# USB_Hub.net
KiCad netlist of a schematic drawn in Altium Designer
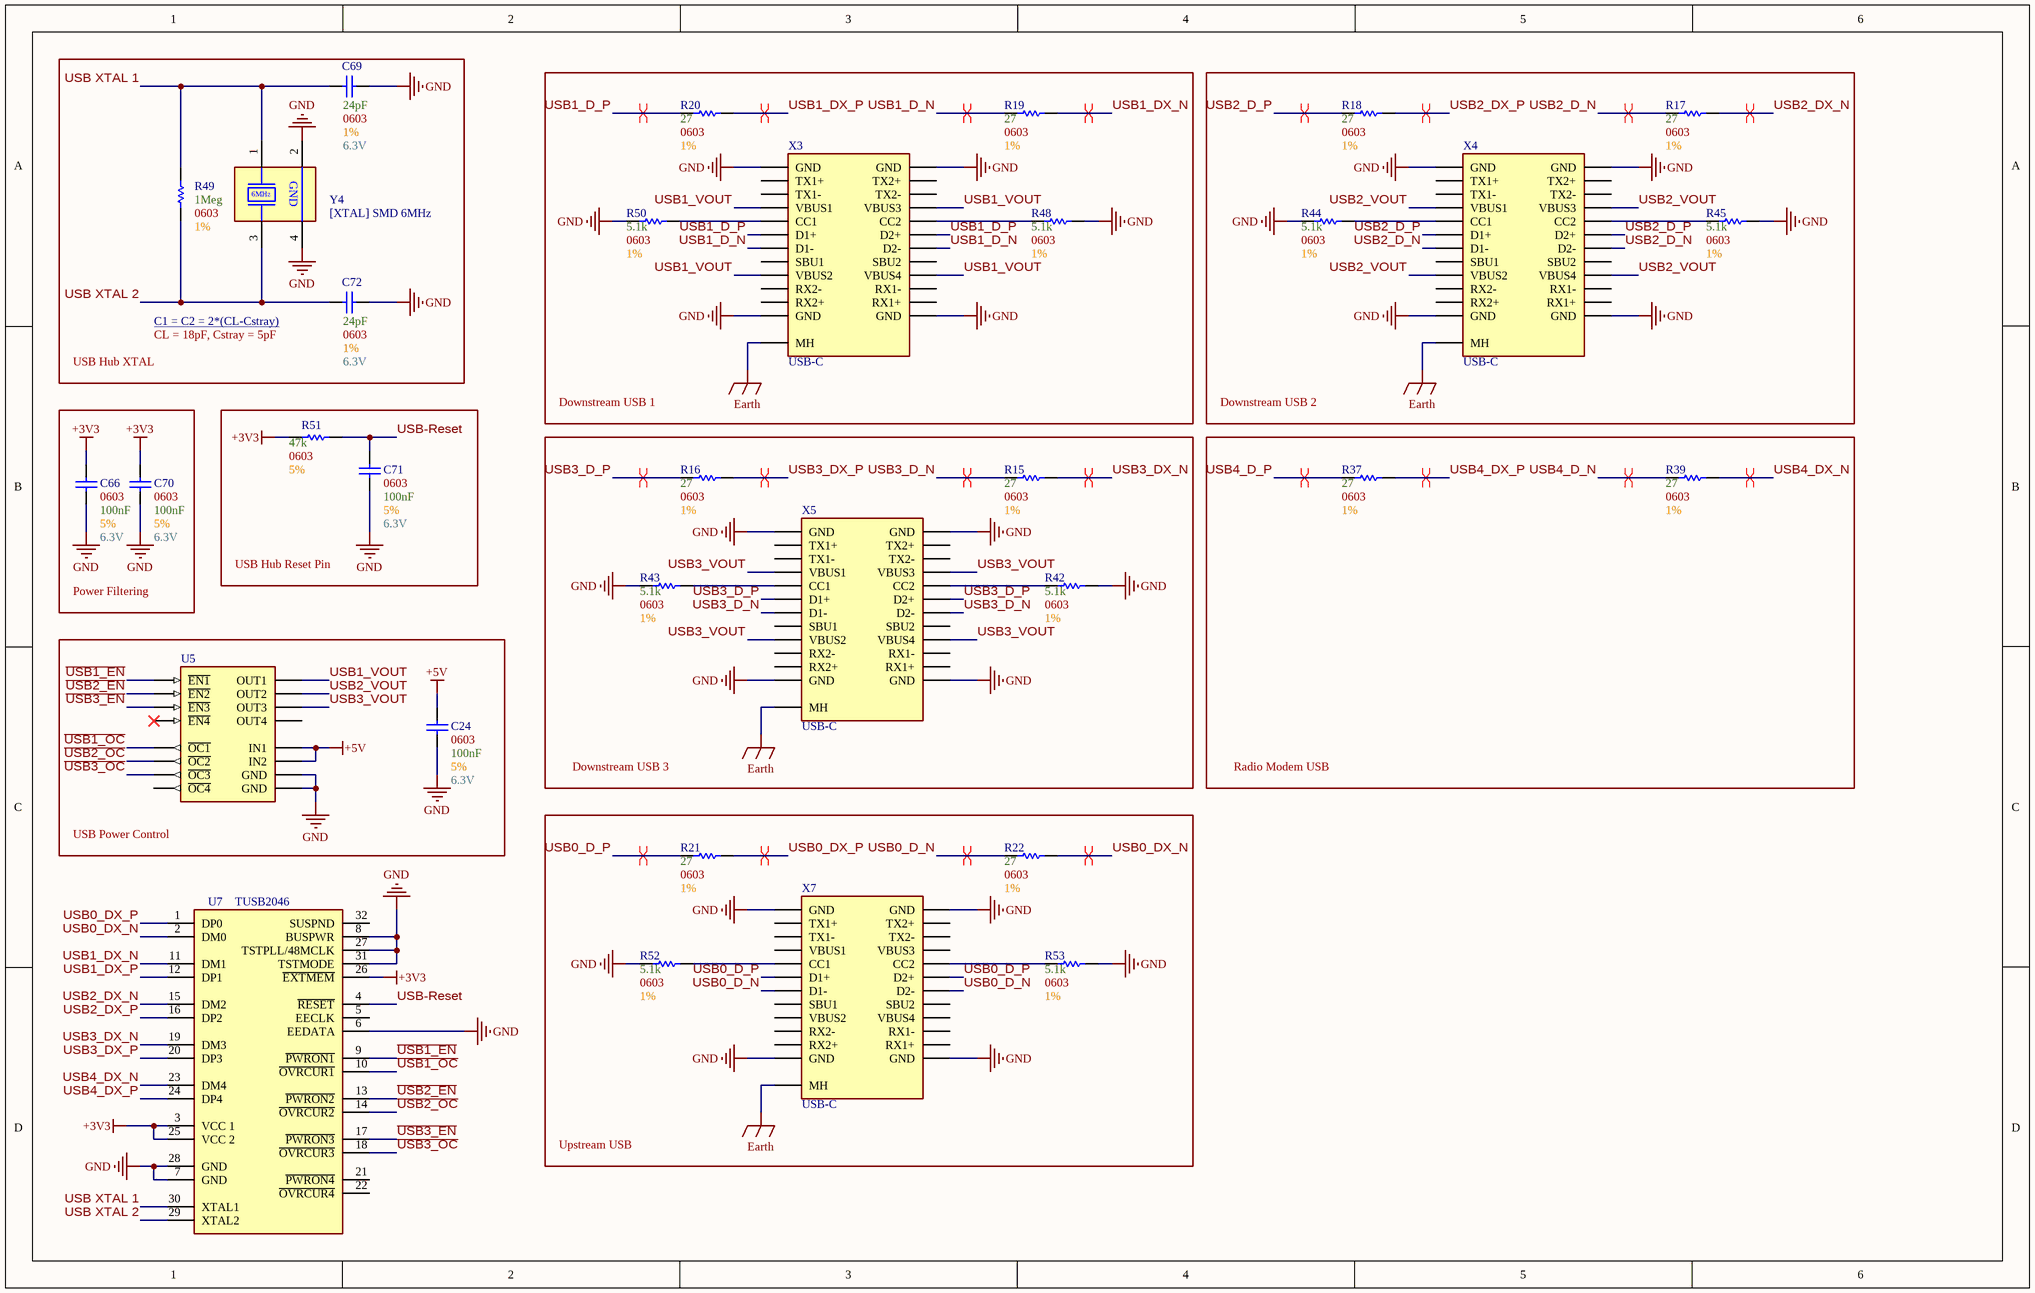
[diagram p0: USB Hub.SchDoc]

(export (version "E")
  (design (tool "Eeschema 10.0.6"))
  (components
    (comp (ref "C24")
      (value "[Cap] SMD Nonpolarized")
      (footprint "[Cap] SMD 0603")
      (fields
        (field (name "SIZE PACKAGE") "0603")
        (field (name "CAPACITANCE") "100nF")
        (field (name "VOLTAGE") "6.3V")
        (field (name "TOLERANCE") "5%")
      )
      (libsource (lib "RADM Components") (part "[Cap] SMD Nonpolarized"))
    )
    (comp (ref "C66")
      (value "[Cap] SMD Nonpolarized")
      (footprint "[Cap] SMD 0603")
      (fields
        (field (name "SIZE PACKAGE") "0603")
        (field (name "CAPACITANCE") "100nF")
        (field (name "VOLTAGE") "6.3V")
        (field (name "TOLERANCE") "5%")
      )
      (libsource (lib "RADM Components") (part "[Cap] SMD Nonpolarized"))
    )
    (comp (ref "C69")
      (value "SMD Nonpolarized")
      (footprint "[Cap] SMD 0603")
      (fields
        (field (name "TOLERANCE") "1%")
        (field (name "SIZE PACKAGE") "0603")
        (field (name "CAPACITANCE") "24pF")
        (field (name "VOLTAGE") "6.3V")
      )
      (libsource (lib "RADM Components") (part "[Cap] SMD Nonpolarized"))
    )
    (comp (ref "C70")
      (value "[Cap] SMD Nonpolarized")
      (footprint "[Cap] SMD 0603")
      (fields
        (field (name "SIZE PACKAGE") "0603")
        (field (name "CAPACITANCE") "100nF")
        (field (name "VOLTAGE") "6.3V")
        (field (name "TOLERANCE") "5%")
      )
      (libsource (lib "RADM Components") (part "[Cap] SMD Nonpolarized"))
    )
    (comp (ref "C71")
      (value "[Cap] SMD Nonpolarized")
      (footprint "[Cap] SMD 0603")
      (fields
        (field (name "SIZE PACKAGE") "0603")
        (field (name "CAPACITANCE") "100nF")
        (field (name "VOLTAGE") "6.3V")
        (field (name "TOLERANCE") "5%")
      )
      (libsource (lib "RADM Components") (part "[Cap] SMD Nonpolarized"))
    )
    (comp (ref "C72")
      (value "SMD Nonpolarized")
      (footprint "[Cap] SMD 0603")
      (fields
        (field (name "TOLERANCE") "1%")
        (field (name "SIZE PACKAGE") "0603")
        (field (name "CAPACITANCE") "24pF")
        (field (name "VOLTAGE") "6.3V")
      )
      (libsource (lib "RADM Components") (part "[Cap] SMD Nonpolarized"))
    )
    (comp (ref "R15")
      (value "[Res] SMD Resistor")
      (footprint "[Res] SMD 0603")
      (description "Generic")
      (fields
        (field (name "TOLERANCE") "1%")
        (field (name "RESISTANCE") "27")
        (field (name "SIZE PACKAGE") "0603")
      )
      (libsource (lib "RADM Components") (part "[Res] SMD Resistor"))
    )
    (comp (ref "R16")
      (value "[Res] SMD Resistor")
      (footprint "[Res] SMD 0603")
      (description "Generic")
      (fields
        (field (name "TOLERANCE") "1%")
        (field (name "RESISTANCE") "27")
        (field (name "SIZE PACKAGE") "0603")
      )
      (libsource (lib "RADM Components") (part "[Res] SMD Resistor"))
    )
    (comp (ref "R17")
      (value "[Res] SMD Resistor")
      (footprint "[Res] SMD 0603")
      (description "Generic")
      (fields
        (field (name "TOLERANCE") "1%")
        (field (name "RESISTANCE") "27")
        (field (name "SIZE PACKAGE") "0603")
      )
      (libsource (lib "RADM Components") (part "[Res] SMD Resistor"))
    )
    (comp (ref "R18")
      (value "[Res] SMD Resistor")
      (footprint "[Res] SMD 0603")
      (description "Generic")
      (fields
        (field (name "TOLERANCE") "1%")
        (field (name "RESISTANCE") "27")
        (field (name "SIZE PACKAGE") "0603")
      )
      (libsource (lib "RADM Components") (part "[Res] SMD Resistor"))
    )
    (comp (ref "R19")
      (value "[Res] SMD Resistor")
      (footprint "[Res] SMD 0603")
      (description "Generic")
      (fields
        (field (name "TOLERANCE") "1%")
        (field (name "RESISTANCE") "27")
        (field (name "SIZE PACKAGE") "0603")
      )
      (libsource (lib "RADM Components") (part "[Res] SMD Resistor"))
    )
    (comp (ref "R20")
      (value "[Res] SMD Resistor")
      (footprint "[Res] SMD 0603")
      (description "Generic")
      (fields
        (field (name "TOLERANCE") "1%")
        (field (name "RESISTANCE") "27")
        (field (name "SIZE PACKAGE") "0603")
      )
      (libsource (lib "RADM Components") (part "[Res] SMD Resistor"))
    )
    (comp (ref "R21")
      (value "[Res] SMD Resistor")
      (footprint "[Res] SMD 0603")
      (description "Generic")
      (fields
        (field (name "TOLERANCE") "1%")
        (field (name "RESISTANCE") "27")
        (field (name "SIZE PACKAGE") "0603")
      )
      (libsource (lib "RADM Components") (part "[Res] SMD Resistor"))
    )
    (comp (ref "R22")
      (value "[Res] SMD Resistor")
      (footprint "[Res] SMD 0603")
      (description "Generic")
      (fields
        (field (name "TOLERANCE") "1%")
        (field (name "RESISTANCE") "27")
        (field (name "SIZE PACKAGE") "0603")
      )
      (libsource (lib "RADM Components") (part "[Res] SMD Resistor"))
    )
    (comp (ref "R37")
      (value "[Res] SMD Resistor")
      (footprint "[Res] SMD 0603")
      (description "Generic")
      (fields
        (field (name "TOLERANCE") "1%")
        (field (name "RESISTANCE") "27")
        (field (name "SIZE PACKAGE") "0603")
      )
      (libsource (lib "RADM Components") (part "[Res] SMD Resistor"))
    )
    (comp (ref "R39")
      (value "[Res] SMD Resistor")
      (footprint "[Res] SMD 0603")
      (description "Generic")
      (fields
        (field (name "TOLERANCE") "1%")
        (field (name "RESISTANCE") "27")
        (field (name "SIZE PACKAGE") "0603")
      )
      (libsource (lib "RADM Components") (part "[Res] SMD Resistor"))
    )
    (comp (ref "R42")
      (value "[Res] SMD Resistor")
      (footprint "[Res] SMD 0603")
      (description "Generic")
      (fields
        (field (name "TOLERANCE") "1%")
        (field (name "RESISTANCE") "5.1k")
        (field (name "SIZE PACKAGE") "0603")
      )
      (libsource (lib "RADM Components") (part "[Res] SMD Resistor"))
    )
    (comp (ref "R43")
      (value "[Res] SMD Resistor")
      (footprint "[Res] SMD 0603")
      (description "Generic")
      (fields
        (field (name "TOLERANCE") "1%")
        (field (name "RESISTANCE") "5.1k")
        (field (name "SIZE PACKAGE") "0603")
      )
      (libsource (lib "RADM Components") (part "[Res] SMD Resistor"))
    )
    (comp (ref "R44")
      (value "[Res] SMD Resistor")
      (footprint "[Res] SMD 0603")
      (description "Generic")
      (fields
        (field (name "TOLERANCE") "1%")
        (field (name "RESISTANCE") "5.1k")
        (field (name "SIZE PACKAGE") "0603")
      )
      (libsource (lib "RADM Components") (part "[Res] SMD Resistor"))
    )
    (comp (ref "R45")
      (value "[Res] SMD Resistor")
      (footprint "[Res] SMD 0603")
      (description "Generic")
      (fields
        (field (name "TOLERANCE") "1%")
        (field (name "RESISTANCE") "5.1k")
        (field (name "SIZE PACKAGE") "0603")
      )
      (libsource (lib "RADM Components") (part "[Res] SMD Resistor"))
    )
    (comp (ref "R48")
      (value "[Res] SMD Resistor")
      (footprint "[Res] SMD 0603")
      (description "Generic")
      (fields
        (field (name "TOLERANCE") "1%")
        (field (name "RESISTANCE") "5.1k")
        (field (name "SIZE PACKAGE") "0603")
      )
      (libsource (lib "RADM Components") (part "[Res] SMD Resistor"))
    )
    (comp (ref "R49")
      (value "[Res] SMD Resistor")
      (footprint "[Res] SMD 0603")
      (description "Generic")
      (fields
        (field (name "TOLERANCE") "1%")
        (field (name "RESISTANCE") "1Meg")
        (field (name "SIZE PACKAGE") "0603")
      )
      (libsource (lib "RADM Components") (part "[Res] SMD Resistor"))
    )
    (comp (ref "R50")
      (value "[Res] SMD Resistor")
      (footprint "[Res] SMD 0603")
      (description "Generic")
      (fields
        (field (name "TOLERANCE") "1%")
        (field (name "RESISTANCE") "5.1k")
        (field (name "SIZE PACKAGE") "0603")
      )
      (libsource (lib "RADM Components") (part "[Res] SMD Resistor"))
    )
    (comp (ref "R51")
      (value "[Res] SMD Resistor")
      (footprint "[Res] SMD 0603")
      (description "Generic")
      (fields
        (field (name "TOLERANCE") "5%")
        (field (name "RESISTANCE") "47k")
        (field (name "SIZE PACKAGE") "0603")
      )
      (libsource (lib "RADM Components") (part "[Res] SMD Resistor"))
    )
    (comp (ref "R52")
      (value "[Res] SMD Resistor")
      (footprint "[Res] SMD 0603")
      (description "Generic")
      (fields
        (field (name "TOLERANCE") "1%")
        (field (name "RESISTANCE") "5.1k")
        (field (name "SIZE PACKAGE") "0603")
      )
      (libsource (lib "RADM Components") (part "[Res] SMD Resistor"))
    )
    (comp (ref "R53")
      (value "[Res] SMD Resistor")
      (footprint "[Res] SMD 0603")
      (description "Generic")
      (fields
        (field (name "TOLERANCE") "1%")
        (field (name "RESISTANCE") "5.1k")
        (field (name "SIZE PACKAGE") "0603")
      )
      (libsource (lib "RADM Components") (part "[Res] SMD Resistor"))
    )
    (comp (ref "U5")
      (value "[IC] USB Hub Power Distribution")
      (footprint "[IC] USB Hub Power Distribution")
      (libsource (lib "RADM Components") (part "[IC] USB Hub Power Distribution"))
    )
    (comp (ref "U7")
      (value "TUSB2046")
      (footprint "[IC] USB Hub 4port (2)")
      (description "TUSB2046BVFR")
      (libsource (lib "RADM Components") (part "[IC] USB Hub 4port (2)"))
    )
    (comp (ref "X3")
      (value "USB-C")
      (footprint "[Port] USB-C")
      (libsource (lib "RADM Connectors") (part "[Port] USB Type-C"))
    )
    (comp (ref "X4")
      (value "USB-C")
      (footprint "[Port] USB-C")
      (libsource (lib "RADM Connectors") (part "[Port] USB Type-C"))
    )
    (comp (ref "X5")
      (value "USB-C")
      (footprint "[Port] USB-C")
      (libsource (lib "RADM Connectors") (part "[Port] USB Type-C"))
    )
    (comp (ref "X7")
      (value "USB-C")
      (footprint "[Port] USB-C")
      (libsource (lib "RADM Connectors") (part "[Port] USB Type-C"))
    )
    (comp (ref "Y4")
      (value "[XTAL] SMD 6MHz")
      (footprint "[XTAL] SMD 6MHz")
      (description "ECS-060-18-20BM-JEN-TR")
      (libsource (lib "RADM Components") (part "[XTAL] SMD 6MHz"))
    )
  )
  (nets
    (net (code "1") (name "+3V3") (class "Default")
      (node (ref "C66") (pin "2") (pinfunction "2_2") (pintype "passive"))
      (node (ref "C70") (pin "2") (pinfunction "2_2") (pintype "passive"))
      (node (ref "R51") (pin "1") (pinfunction "1_1") (pintype "passive"))
      (node (ref "U7") (pin "25") (pinfunction "VCC_2_25") (pintype "passive"))
      (node (ref "U7") (pin "26") (pinfunction "~{EXTMEM}_26") (pintype "passive"))
      (node (ref "U7") (pin "3") (pinfunction "VCC_1_3") (pintype "passive"))
    )
    (net (code "2") (name "+5V") (class "Default")
      (node (ref "C24") (pin "2") (pinfunction "2_2") (pintype "passive"))
      (node (ref "U5") (pin "2") (pinfunction "IN1_2") (pintype "power_in"))
      (node (ref "U5") (pin "6") (pinfunction "IN2_6") (pintype "power_in"))
    )
    (net (code "3") (name "/USB XTAL 1") (class "Default")
      (node (ref "C69") (pin "1") (pinfunction "1_1") (pintype "passive"))
      (node (ref "R49") (pin "1") (pinfunction "1_1") (pintype "passive"))
      (node (ref "U7") (pin "30") (pinfunction "XTAL1_30") (pintype "passive"))
      (node (ref "Y4") (pin "1") (pinfunction "XTAL1_1") (pintype "power_in"))
    )
    (net (code "4") (name "/USB XTAL 2") (class "Default")
      (node (ref "C72") (pin "1") (pinfunction "1_1") (pintype "passive"))
      (node (ref "R49") (pin "2") (pinfunction "2_2") (pintype "passive"))
      (node (ref "U7") (pin "29") (pinfunction "XTAL2_29") (pintype "passive"))
      (node (ref "Y4") (pin "3") (pinfunction "XTAL2_3") (pintype "power_in"))
    )
    (net (code "5") (name "/USB-Reset") (class "Default")
      (node (ref "C71") (pin "2") (pinfunction "2_2") (pintype "passive"))
      (node (ref "R51") (pin "2") (pinfunction "2_2") (pintype "passive"))
      (node (ref "U7") (pin "4") (pinfunction "~{RESET}_4") (pintype "passive"))
    )
    (net (code "6") (name "/USB0_DX_N") (class "Default")
      (node (ref "R22") (pin "2") (pinfunction "2_2") (pintype "passive"))
      (node (ref "U7") (pin "2") (pinfunction "DM0_2") (pintype "passive"))
    )
    (net (code "7") (name "/USB0_DX_P") (class "Default")
      (node (ref "R21") (pin "2") (pinfunction "2_2") (pintype "passive"))
      (node (ref "U7") (pin "1") (pinfunction "DP0_1") (pintype "passive"))
    )
    (net (code "8") (name "/USB0_D_N") (class "Default")
      (node (ref "R22") (pin "1") (pinfunction "1_1") (pintype "passive"))
      (node (ref "X7") (pin "A7") (pinfunction "D1-_A7") (pintype "passive"))
      (node (ref "X7") (pin "B7") (pinfunction "D2-_B7") (pintype "passive"))
    )
    (net (code "9") (name "/USB0_D_P") (class "Default")
      (node (ref "R21") (pin "1") (pinfunction "1_1") (pintype "passive"))
      (node (ref "X7") (pin "A6") (pinfunction "D1+_A6") (pintype "passive"))
      (node (ref "X7") (pin "B6") (pinfunction "D2+_B6") (pintype "passive"))
    )
    (net (code "10") (name "/USB1_DX_N") (class "Default")
      (node (ref "R19") (pin "2") (pinfunction "2_2") (pintype "passive"))
      (node (ref "U7") (pin "11") (pinfunction "DM1_11") (pintype "passive"))
    )
    (net (code "11") (name "/USB1_DX_P") (class "Default")
      (node (ref "R20") (pin "2") (pinfunction "2_2") (pintype "passive"))
      (node (ref "U7") (pin "12") (pinfunction "DP1_12") (pintype "passive"))
    )
    (net (code "12") (name "/USB1_D_N") (class "Default")
      (node (ref "R19") (pin "1") (pinfunction "1_1") (pintype "passive"))
      (node (ref "X3") (pin "A7") (pinfunction "D1-_A7") (pintype "passive"))
      (node (ref "X3") (pin "B7") (pinfunction "D2-_B7") (pintype "passive"))
    )
    (net (code "13") (name "/USB1_D_P") (class "Default")
      (node (ref "R20") (pin "1") (pinfunction "1_1") (pintype "passive"))
      (node (ref "X3") (pin "A6") (pinfunction "D1+_A6") (pintype "passive"))
      (node (ref "X3") (pin "B6") (pinfunction "D2+_B6") (pintype "passive"))
    )
    (net (code "14") (name "/USB1_EN") (class "Default")
      (node (ref "U5") (pin "3") (pinfunction "~{EN1}_3") (pintype "input"))
      (node (ref "U7") (pin "9") (pinfunction "~{PWRON1}_9") (pintype "passive"))
    )
    (net (code "15") (name "/USB1_OC") (class "Default")
      (node (ref "U5") (pin "16") (pinfunction "~{OC1}_16") (pintype "output"))
      (node (ref "U7") (pin "10") (pinfunction "~{OVRCUR1}_10") (pintype "passive"))
    )
    (net (code "16") (name "/USB1_VOUT") (class "Default")
      (node (ref "U5") (pin "15") (pinfunction "OUT1_15") (pintype "power_in"))
      (node (ref "X3") (pin "A4") (pinfunction "VBUS1_A4") (pintype "passive"))
      (node (ref "X3") (pin "A9") (pinfunction "VBUS2_A9") (pintype "passive"))
      (node (ref "X3") (pin "B4") (pinfunction "VBUS3_B4") (pintype "passive"))
      (node (ref "X3") (pin "B9") (pinfunction "VBUS4_B9") (pintype "passive"))
    )
    (net (code "17") (name "/USB2_DX_N") (class "Default")
      (node (ref "R17") (pin "2") (pinfunction "2_2") (pintype "passive"))
      (node (ref "U7") (pin "15") (pinfunction "DM2_15") (pintype "passive"))
    )
    (net (code "18") (name "/USB2_DX_P") (class "Default")
      (node (ref "R18") (pin "2") (pinfunction "2_2") (pintype "passive"))
      (node (ref "U7") (pin "16") (pinfunction "DP2_16") (pintype "passive"))
    )
    (net (code "19") (name "/USB2_D_N") (class "Default")
      (node (ref "R17") (pin "1") (pinfunction "1_1") (pintype "passive"))
      (node (ref "X4") (pin "A7") (pinfunction "D1-_A7") (pintype "passive"))
      (node (ref "X4") (pin "B7") (pinfunction "D2-_B7") (pintype "passive"))
    )
    (net (code "20") (name "/USB2_D_P") (class "Default")
      (node (ref "R18") (pin "1") (pinfunction "1_1") (pintype "passive"))
      (node (ref "X4") (pin "A6") (pinfunction "D1+_A6") (pintype "passive"))
      (node (ref "X4") (pin "B6") (pinfunction "D2+_B6") (pintype "passive"))
    )
    (net (code "21") (name "/USB2_EN") (class "Default")
      (node (ref "U5") (pin "4") (pinfunction "~{EN2}_4") (pintype "input"))
      (node (ref "U7") (pin "13") (pinfunction "~{PWRON2}_13") (pintype "passive"))
    )
    (net (code "22") (name "/USB2_OC") (class "Default")
      (node (ref "U5") (pin "13") (pinfunction "~{OC2}_13") (pintype "output"))
      (node (ref "U7") (pin "14") (pinfunction "~{OVRCUR2}_14") (pintype "passive"))
    )
    (net (code "23") (name "/USB2_VOUT") (class "Default")
      (node (ref "U5") (pin "14") (pinfunction "OUT2_14") (pintype "power_in"))
      (node (ref "X4") (pin "A4") (pinfunction "VBUS1_A4") (pintype "passive"))
      (node (ref "X4") (pin "A9") (pinfunction "VBUS2_A9") (pintype "passive"))
      (node (ref "X4") (pin "B4") (pinfunction "VBUS3_B4") (pintype "passive"))
      (node (ref "X4") (pin "B9") (pinfunction "VBUS4_B9") (pintype "passive"))
    )
    (net (code "24") (name "/USB3_DX_N") (class "Default")
      (node (ref "R15") (pin "2") (pinfunction "2_2") (pintype "passive"))
      (node (ref "U7") (pin "19") (pinfunction "DM3_19") (pintype "passive"))
    )
    (net (code "25") (name "/USB3_DX_P") (class "Default")
      (node (ref "R16") (pin "2") (pinfunction "2_2") (pintype "passive"))
      (node (ref "U7") (pin "20") (pinfunction "DP3_20") (pintype "passive"))
    )
    (net (code "26") (name "/USB3_D_N") (class "Default")
      (node (ref "R15") (pin "1") (pinfunction "1_1") (pintype "passive"))
      (node (ref "X5") (pin "A7") (pinfunction "D1-_A7") (pintype "passive"))
      (node (ref "X5") (pin "B7") (pinfunction "D2-_B7") (pintype "passive"))
    )
    (net (code "27") (name "/USB3_D_P") (class "Default")
      (node (ref "R16") (pin "1") (pinfunction "1_1") (pintype "passive"))
      (node (ref "X5") (pin "A6") (pinfunction "D1+_A6") (pintype "passive"))
      (node (ref "X5") (pin "B6") (pinfunction "D2+_B6") (pintype "passive"))
    )
    (net (code "28") (name "/USB3_EN") (class "Default")
      (node (ref "U5") (pin "7") (pinfunction "~{EN3}_7") (pintype "input"))
      (node (ref "U7") (pin "17") (pinfunction "~{PWRON3}_17") (pintype "passive"))
    )
    (net (code "29") (name "/USB3_OC") (class "Default")
      (node (ref "U5") (pin "12") (pinfunction "~{OC3}_12") (pintype "output"))
      (node (ref "U7") (pin "18") (pinfunction "~{OVRCUR3}_18") (pintype "passive"))
    )
    (net (code "30") (name "/USB3_VOUT") (class "Default")
      (node (ref "U5") (pin "11") (pinfunction "OUT3_11") (pintype "power_in"))
      (node (ref "X5") (pin "A4") (pinfunction "VBUS1_A4") (pintype "passive"))
      (node (ref "X5") (pin "A9") (pinfunction "VBUS2_A9") (pintype "passive"))
      (node (ref "X5") (pin "B4") (pinfunction "VBUS3_B4") (pintype "passive"))
      (node (ref "X5") (pin "B9") (pinfunction "VBUS4_B9") (pintype "passive"))
    )
    (net (code "31") (name "/USB4_DX_N") (class "Default")
      (node (ref "R39") (pin "2") (pinfunction "2_2") (pintype "passive"))
      (node (ref "U7") (pin "23") (pinfunction "DM4_23") (pintype "passive"))
    )
    (net (code "32") (name "/USB4_DX_P") (class "Default")
      (node (ref "R37") (pin "2") (pinfunction "2_2") (pintype "passive"))
      (node (ref "U7") (pin "24") (pinfunction "DP4_24") (pintype "passive"))
    )
    (net (code "33") (name "/USB4_D_N") (class "Default")
      (node (ref "R39") (pin "1") (pinfunction "1_1") (pintype "passive"))
    )
    (net (code "34") (name "/USB4_D_P") (class "Default")
      (node (ref "R37") (pin "1") (pinfunction "1_1") (pintype "passive"))
    )
    (net (code "35") (name "Earth") (class "Default")
      (node (ref "X3") (pin "MH") (pinfunction "MH_MH") (pintype "passive"))
      (node (ref "X4") (pin "MH") (pinfunction "MH_MH") (pintype "passive"))
      (node (ref "X5") (pin "MH") (pinfunction "MH_MH") (pintype "passive"))
      (node (ref "X7") (pin "MH") (pinfunction "MH_MH") (pintype "passive"))
    )
    (net (code "36") (name "GND") (class "Default")
      (node (ref "C24") (pin "1") (pinfunction "1_1") (pintype "passive"))
      (node (ref "C66") (pin "1") (pinfunction "1_1") (pintype "passive"))
      (node (ref "C69") (pin "2") (pinfunction "2_2") (pintype "passive"))
      (node (ref "C70") (pin "1") (pinfunction "1_1") (pintype "passive"))
      (node (ref "C71") (pin "1") (pinfunction "1_1") (pintype "passive"))
      (node (ref "C72") (pin "2") (pinfunction "2_2") (pintype "passive"))
      (node (ref "R42") (pin "2") (pinfunction "2_2") (pintype "passive"))
      (node (ref "R43") (pin "1") (pinfunction "1_1") (pintype "passive"))
      (node (ref "R44") (pin "1") (pinfunction "1_1") (pintype "passive"))
      (node (ref "R45") (pin "2") (pinfunction "2_2") (pintype "passive"))
      (node (ref "R48") (pin "2") (pinfunction "2_2") (pintype "passive"))
      (node (ref "R50") (pin "1") (pinfunction "1_1") (pintype "passive"))
      (node (ref "R52") (pin "1") (pinfunction "1_1") (pintype "passive"))
      (node (ref "R53") (pin "2") (pinfunction "2_2") (pintype "passive"))
      (node (ref "U5") (pin "1") (pinfunction "GND_1") (pintype "power_in"))
      (node (ref "U5") (pin "5") (pinfunction "GND_5") (pintype "power_in"))
      (node (ref "U7") (pin "27") (pinfunction "TSTPLL/48MCLK_27") (pintype "passive"))
      (node (ref "U7") (pin "28") (pinfunction "GND_28") (pintype "passive"))
      (node (ref "U7") (pin "31") (pinfunction "TSTMODE_31") (pintype "passive"))
      (node (ref "U7") (pin "6") (pinfunction "EEDATA_6") (pintype "passive"))
      (node (ref "U7") (pin "7") (pinfunction "GND_7") (pintype "passive"))
      (node (ref "U7") (pin "8") (pinfunction "BUSPWR_8") (pintype "passive"))
      (node (ref "X3") (pin "A1") (pinfunction "GND_A1") (pintype "passive"))
      (node (ref "X3") (pin "A12") (pinfunction "GND_A12") (pintype "passive"))
      (node (ref "X3") (pin "B1") (pinfunction "GND_B1") (pintype "passive"))
      (node (ref "X3") (pin "B12") (pinfunction "GND_B12") (pintype "passive"))
      (node (ref "X4") (pin "A1") (pinfunction "GND_A1") (pintype "passive"))
      (node (ref "X4") (pin "A12") (pinfunction "GND_A12") (pintype "passive"))
      (node (ref "X4") (pin "B1") (pinfunction "GND_B1") (pintype "passive"))
      (node (ref "X4") (pin "B12") (pinfunction "GND_B12") (pintype "passive"))
      (node (ref "X5") (pin "A1") (pinfunction "GND_A1") (pintype "passive"))
      (node (ref "X5") (pin "A12") (pinfunction "GND_A12") (pintype "passive"))
      (node (ref "X5") (pin "B1") (pinfunction "GND_B1") (pintype "passive"))
      (node (ref "X5") (pin "B12") (pinfunction "GND_B12") (pintype "passive"))
      (node (ref "X7") (pin "A1") (pinfunction "GND_A1") (pintype "passive"))
      (node (ref "X7") (pin "A12") (pinfunction "GND_A12") (pintype "passive"))
      (node (ref "X7") (pin "B1") (pinfunction "GND_B1") (pintype "passive"))
      (node (ref "X7") (pin "B12") (pinfunction "GND_B12") (pintype "passive"))
      (node (ref "Y4") (pin "2") (pinfunction "GND_2") (pintype "power_in"))
      (node (ref "Y4") (pin "4") (pinfunction "GND_4") (pintype "power_in"))
    )
    (net (code "37") (name "Net-(X3-CC1)") (class "Default")
      (node (ref "R50") (pin "2") (pinfunction "2_2") (pintype "passive"))
      (node (ref "X3") (pin "A5") (pinfunction "CC1_A5") (pintype "passive"))
    )
    (net (code "38") (name "Net-(X3-CC2)") (class "Default")
      (node (ref "R48") (pin "1") (pinfunction "1_1") (pintype "passive"))
      (node (ref "X3") (pin "B5") (pinfunction "CC2_B5") (pintype "passive"))
    )
    (net (code "39") (name "Net-(X4-CC1)") (class "Default")
      (node (ref "R44") (pin "2") (pinfunction "2_2") (pintype "passive"))
      (node (ref "X4") (pin "A5") (pinfunction "CC1_A5") (pintype "passive"))
    )
    (net (code "40") (name "Net-(X4-CC2)") (class "Default")
      (node (ref "R45") (pin "1") (pinfunction "1_1") (pintype "passive"))
      (node (ref "X4") (pin "B5") (pinfunction "CC2_B5") (pintype "passive"))
    )
    (net (code "41") (name "Net-(X5-CC1)") (class "Default")
      (node (ref "R43") (pin "2") (pinfunction "2_2") (pintype "passive"))
      (node (ref "X5") (pin "A5") (pinfunction "CC1_A5") (pintype "passive"))
    )
    (net (code "42") (name "Net-(X5-CC2)") (class "Default")
      (node (ref "R42") (pin "1") (pinfunction "1_1") (pintype "passive"))
      (node (ref "X5") (pin "B5") (pinfunction "CC2_B5") (pintype "passive"))
    )
    (net (code "43") (name "Net-(X7-CC1)") (class "Default")
      (node (ref "R52") (pin "2") (pinfunction "2_2") (pintype "passive"))
      (node (ref "X7") (pin "A5") (pinfunction "CC1_A5") (pintype "passive"))
    )
    (net (code "44") (name "Net-(X7-CC2)") (class "Default")
      (node (ref "R53") (pin "1") (pinfunction "1_1") (pintype "passive"))
      (node (ref "X7") (pin "B5") (pinfunction "CC2_B5") (pintype "passive"))
    )
    (net (code "45") (name "unconnected-(U5-OUT4-Pad10)") (class "Default")
      (node (ref "U5") (pin "10") (pinfunction "OUT4_10") (pintype "power_in"))
    )
    (net (code "46") (name "unconnected-(U5-~{EN4}-Pad8)") (class "Default")
      (node (ref "U5") (pin "8") (pinfunction "~{EN4}_8") (pintype "input+no_connect"))
    )
    (net (code "47") (name "unconnected-(U5-~{OC4}-Pad9)") (class "Default")
      (node (ref "U5") (pin "9") (pinfunction "~{OC4}_9") (pintype "output"))
    )
    (net (code "48") (name "unconnected-(U7-EECLK-Pad5)") (class "Default")
      (node (ref "U7") (pin "5") (pinfunction "EECLK_5") (pintype "passive"))
    )
    (net (code "49") (name "unconnected-(U7-SUSPND-Pad32)") (class "Default")
      (node (ref "U7") (pin "32") (pinfunction "SUSPND_32") (pintype "passive"))
    )
    (net (code "50") (name "unconnected-(U7-~{OVRCUR4}-Pad22)") (class "Default")
      (node (ref "U7") (pin "22") (pinfunction "~{OVRCUR4}_22") (pintype "passive"))
    )
    (net (code "51") (name "unconnected-(U7-~{PWRON4}-Pad21)") (class "Default")
      (node (ref "U7") (pin "21") (pinfunction "~{PWRON4}_21") (pintype "passive"))
    )
    (net (code "52") (name "unconnected-(X3-RX1+-PadB11)") (class "Default")
      (node (ref "X3") (pin "B11") (pinfunction "RX1+_B11") (pintype "passive"))
    )
    (net (code "53") (name "unconnected-(X3-RX1--PadB10)") (class "Default")
      (node (ref "X3") (pin "B10") (pinfunction "RX1-_B10") (pintype "passive"))
    )
    (net (code "54") (name "unconnected-(X3-RX2+-PadA11)") (class "Default")
      (node (ref "X3") (pin "A11") (pinfunction "RX2+_A11") (pintype "passive"))
    )
    (net (code "55") (name "unconnected-(X3-RX2--PadA10)") (class "Default")
      (node (ref "X3") (pin "A10") (pinfunction "RX2-_A10") (pintype "passive"))
    )
    (net (code "56") (name "unconnected-(X3-SBU1-PadA8)") (class "Default")
      (node (ref "X3") (pin "A8") (pinfunction "SBU1_A8") (pintype "passive"))
    )
    (net (code "57") (name "unconnected-(X3-SBU2-PadB8)") (class "Default")
      (node (ref "X3") (pin "B8") (pinfunction "SBU2_B8") (pintype "passive"))
    )
    (net (code "58") (name "unconnected-(X3-TX1+-PadA2)") (class "Default")
      (node (ref "X3") (pin "A2") (pinfunction "TX1+_A2") (pintype "passive"))
    )
    (net (code "59") (name "unconnected-(X3-TX1--PadA3)") (class "Default")
      (node (ref "X3") (pin "A3") (pinfunction "TX1-_A3") (pintype "passive"))
    )
    (net (code "60") (name "unconnected-(X3-TX2+-PadB2)") (class "Default")
      (node (ref "X3") (pin "B2") (pinfunction "TX2+_B2") (pintype "passive"))
    )
    (net (code "61") (name "unconnected-(X3-TX2--PadB3)") (class "Default")
      (node (ref "X3") (pin "B3") (pinfunction "TX2-_B3") (pintype "passive"))
    )
    (net (code "62") (name "unconnected-(X4-RX1+-PadB11)") (class "Default")
      (node (ref "X4") (pin "B11") (pinfunction "RX1+_B11") (pintype "passive"))
    )
    (net (code "63") (name "unconnected-(X4-RX1--PadB10)") (class "Default")
      (node (ref "X4") (pin "B10") (pinfunction "RX1-_B10") (pintype "passive"))
    )
    (net (code "64") (name "unconnected-(X4-RX2+-PadA11)") (class "Default")
      (node (ref "X4") (pin "A11") (pinfunction "RX2+_A11") (pintype "passive"))
    )
    (net (code "65") (name "unconnected-(X4-RX2--PadA10)") (class "Default")
      (node (ref "X4") (pin "A10") (pinfunction "RX2-_A10") (pintype "passive"))
    )
    (net (code "66") (name "unconnected-(X4-SBU1-PadA8)") (class "Default")
      (node (ref "X4") (pin "A8") (pinfunction "SBU1_A8") (pintype "passive"))
    )
    (net (code "67") (name "unconnected-(X4-SBU2-PadB8)") (class "Default")
      (node (ref "X4") (pin "B8") (pinfunction "SBU2_B8") (pintype "passive"))
    )
    (net (code "68") (name "unconnected-(X4-TX1+-PadA2)") (class "Default")
      (node (ref "X4") (pin "A2") (pinfunction "TX1+_A2") (pintype "passive"))
    )
    (net (code "69") (name "unconnected-(X4-TX1--PadA3)") (class "Default")
      (node (ref "X4") (pin "A3") (pinfunction "TX1-_A3") (pintype "passive"))
    )
    (net (code "70") (name "unconnected-(X4-TX2+-PadB2)") (class "Default")
      (node (ref "X4") (pin "B2") (pinfunction "TX2+_B2") (pintype "passive"))
    )
    (net (code "71") (name "unconnected-(X4-TX2--PadB3)") (class "Default")
      (node (ref "X4") (pin "B3") (pinfunction "TX2-_B3") (pintype "passive"))
    )
    (net (code "72") (name "unconnected-(X5-RX1+-PadB11)") (class "Default")
      (node (ref "X5") (pin "B11") (pinfunction "RX1+_B11") (pintype "passive"))
    )
    (net (code "73") (name "unconnected-(X5-RX1--PadB10)") (class "Default")
      (node (ref "X5") (pin "B10") (pinfunction "RX1-_B10") (pintype "passive"))
    )
    (net (code "74") (name "unconnected-(X5-RX2+-PadA11)") (class "Default")
      (node (ref "X5") (pin "A11") (pinfunction "RX2+_A11") (pintype "passive"))
    )
    (net (code "75") (name "unconnected-(X5-RX2--PadA10)") (class "Default")
      (node (ref "X5") (pin "A10") (pinfunction "RX2-_A10") (pintype "passive"))
    )
    (net (code "76") (name "unconnected-(X5-SBU1-PadA8)") (class "Default")
      (node (ref "X5") (pin "A8") (pinfunction "SBU1_A8") (pintype "passive"))
    )
    (net (code "77") (name "unconnected-(X5-SBU2-PadB8)") (class "Default")
      (node (ref "X5") (pin "B8") (pinfunction "SBU2_B8") (pintype "passive"))
    )
    (net (code "78") (name "unconnected-(X5-TX1+-PadA2)") (class "Default")
      (node (ref "X5") (pin "A2") (pinfunction "TX1+_A2") (pintype "passive"))
    )
    (net (code "79") (name "unconnected-(X5-TX1--PadA3)") (class "Default")
      (node (ref "X5") (pin "A3") (pinfunction "TX1-_A3") (pintype "passive"))
    )
    (net (code "80") (name "unconnected-(X5-TX2+-PadB2)") (class "Default")
      (node (ref "X5") (pin "B2") (pinfunction "TX2+_B2") (pintype "passive"))
    )
    (net (code "81") (name "unconnected-(X5-TX2--PadB3)") (class "Default")
      (node (ref "X5") (pin "B3") (pinfunction "TX2-_B3") (pintype "passive"))
    )
    (net (code "82") (name "unconnected-(X7-RX1+-PadB11)") (class "Default")
      (node (ref "X7") (pin "B11") (pinfunction "RX1+_B11") (pintype "passive"))
    )
    (net (code "83") (name "unconnected-(X7-RX1--PadB10)") (class "Default")
      (node (ref "X7") (pin "B10") (pinfunction "RX1-_B10") (pintype "passive"))
    )
    (net (code "84") (name "unconnected-(X7-RX2+-PadA11)") (class "Default")
      (node (ref "X7") (pin "A11") (pinfunction "RX2+_A11") (pintype "passive"))
    )
    (net (code "85") (name "unconnected-(X7-RX2--PadA10)") (class "Default")
      (node (ref "X7") (pin "A10") (pinfunction "RX2-_A10") (pintype "passive"))
    )
    (net (code "86") (name "unconnected-(X7-SBU1-PadA8)") (class "Default")
      (node (ref "X7") (pin "A8") (pinfunction "SBU1_A8") (pintype "passive"))
    )
    (net (code "87") (name "unconnected-(X7-SBU2-PadB8)") (class "Default")
      (node (ref "X7") (pin "B8") (pinfunction "SBU2_B8") (pintype "passive"))
    )
    (net (code "88") (name "unconnected-(X7-TX1+-PadA2)") (class "Default")
      (node (ref "X7") (pin "A2") (pinfunction "TX1+_A2") (pintype "passive"))
    )
    (net (code "89") (name "unconnected-(X7-TX1--PadA3)") (class "Default")
      (node (ref "X7") (pin "A3") (pinfunction "TX1-_A3") (pintype "passive"))
    )
    (net (code "90") (name "unconnected-(X7-TX2+-PadB2)") (class "Default")
      (node (ref "X7") (pin "B2") (pinfunction "TX2+_B2") (pintype "passive"))
    )
    (net (code "91") (name "unconnected-(X7-TX2--PadB3)") (class "Default")
      (node (ref "X7") (pin "B3") (pinfunction "TX2-_B3") (pintype "passive"))
    )
    (net (code "92") (name "unconnected-(X7-VBUS1-PadA4)") (class "Default")
      (node (ref "X7") (pin "A4") (pinfunction "VBUS1_A4") (pintype "passive"))
    )
    (net (code "93") (name "unconnected-(X7-VBUS2-PadA9)") (class "Default")
      (node (ref "X7") (pin "A9") (pinfunction "VBUS2_A9") (pintype "passive"))
    )
    (net (code "94") (name "unconnected-(X7-VBUS3-PadB4)") (class "Default")
      (node (ref "X7") (pin "B4") (pinfunction "VBUS3_B4") (pintype "passive"))
    )
    (net (code "95") (name "unconnected-(X7-VBUS4-PadB9)") (class "Default")
      (node (ref "X7") (pin "B9") (pinfunction "VBUS4_B9") (pintype "passive"))
    )
  )
)
